# LDR_circuit.net
KiCad netlist of a schematic drawn in EAGLE
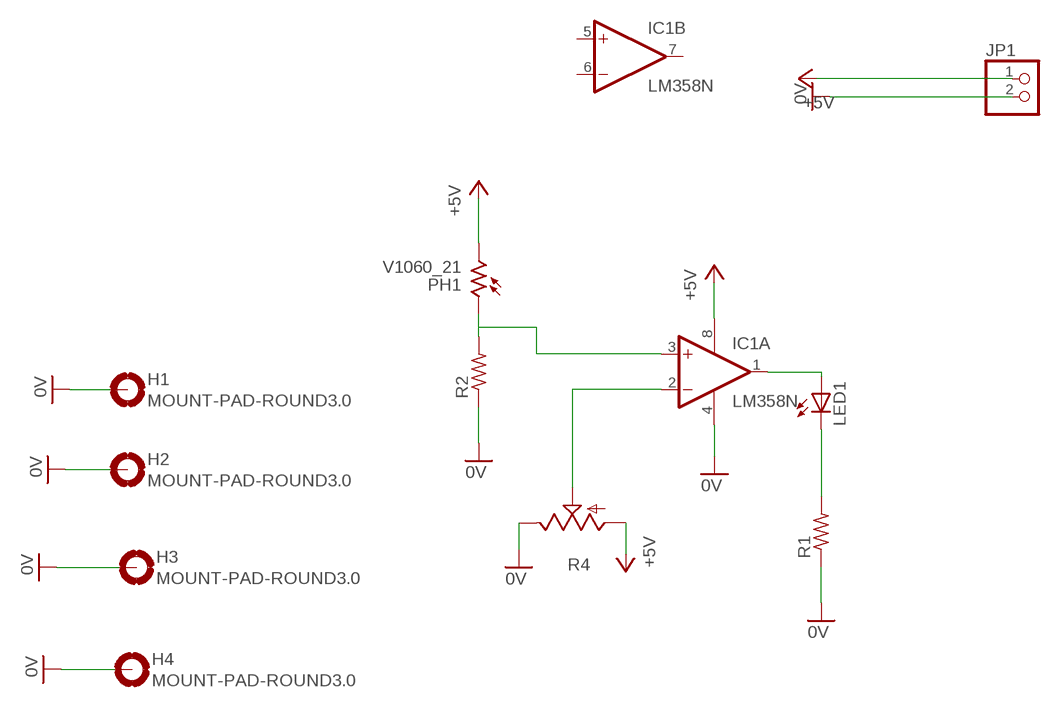
[diagram p0: schematic, sheet 1]

(export (version "E")
  (design (tool "Eeschema 10.0.6"))
  (components
    (comp (ref "H1")
      (value "MOUNT-PAD-ROUND3.0")
      (footprint "eagle-import:3,0-PAD")
      (libsource (lib "eagle-import") (part "MOUNT-PAD-ROUND3.0"))
    )
    (comp (ref "H2")
      (value "MOUNT-PAD-ROUND3.0")
      (footprint "eagle-import:3,0-PAD")
      (libsource (lib "eagle-import") (part "MOUNT-PAD-ROUND3.0"))
    )
    (comp (ref "H3")
      (value "MOUNT-PAD-ROUND3.0")
      (footprint "eagle-import:3,0-PAD")
      (libsource (lib "eagle-import") (part "MOUNT-PAD-ROUND3.0"))
    )
    (comp (ref "H4")
      (value "MOUNT-PAD-ROUND3.0")
      (footprint "eagle-import:3,0-PAD")
      (libsource (lib "eagle-import") (part "MOUNT-PAD-ROUND3.0"))
    )
    (comp (ref "IC1")
      (value "LM358N")
      (footprint "eagle-import:DIL08")
      (libsource (lib "eagle-import") (part "LM358N"))
    )
    (comp (ref "JP1")
      (value "PINHD-1X2")
      (footprint "eagle-import:1X02")
      (libsource (lib "eagle-import") (part "PINHD-1X2"))
    )
    (comp (ref "LED1")
      (value "LED5MM")
      (footprint "eagle-import:LED5MM")
      (libsource (lib "eagle-import") (part "LED5MM"))
    )
    (comp (ref "PH1")
      (value "V1060_21")
      (footprint "eagle-import:TO-5_V10")
      (libsource (lib "eagle-import") (part "?1060V_21"))
    )
    (comp (ref "R1")
      (value "R-US_0207/10")
      (footprint "eagle-import:0207_10")
      (libsource (lib "eagle-import") (part "R-US_0207/10"))
    )
    (comp (ref "R2")
      (value "R-US_0207/10")
      (footprint "eagle-import:0207_10")
      (libsource (lib "eagle-import") (part "R-US_0207/10"))
    )
    (comp (ref "R4")
      (value "TRIM_US-CA6V")
      (footprint "eagle-import:CA6V")
      (libsource (lib "eagle-import") (part "TRIM_US-CA6V"))
    )
  )
  (nets
    (net (code "1") (name "+5V") (class "Default")
      (node (ref "IC1") (pin "8") (pinfunction "V+_8") (pintype "power_in"))
      (node (ref "JP1") (pin "1") (pinfunction "1_1") (pintype "passive"))
      (node (ref "PH1") (pin "2") (pinfunction "2_2") (pintype "passive"))
      (node (ref "R4") (pin "A") (pinfunction "A_A") (pintype "passive"))
    )
    (net (code "2") (name "0V") (class "Default")
      (node (ref "H1") (pin "B3,0") (pinfunction "MOUNT_B3,0") (pintype "passive"))
      (node (ref "H2") (pin "B3,0") (pinfunction "MOUNT_B3,0") (pintype "passive"))
      (node (ref "H3") (pin "B3,0") (pinfunction "MOUNT_B3,0") (pintype "passive"))
      (node (ref "H4") (pin "B3,0") (pinfunction "MOUNT_B3,0") (pintype "passive"))
      (node (ref "IC1") (pin "4") (pinfunction "V-_4") (pintype "power_in"))
      (node (ref "JP1") (pin "2") (pinfunction "2_2") (pintype "passive"))
      (node (ref "R1") (pin "1") (pinfunction "1_1") (pintype "passive"))
      (node (ref "R2") (pin "1") (pinfunction "1_1") (pintype "passive"))
      (node (ref "R4") (pin "E") (pinfunction "E_E") (pintype "passive"))
    )
    (net (code "3") (name "Net-(IC1A-+IN)") (class "Default")
      (node (ref "IC1") (pin "3") (pinfunction "+IN_3") (pintype "input"))
      (node (ref "PH1") (pin "1") (pinfunction "1_1") (pintype "passive"))
      (node (ref "R2") (pin "2") (pinfunction "2_2") (pintype "passive"))
    )
    (net (code "4") (name "Net-(IC1A--IN)") (class "Default")
      (node (ref "IC1") (pin "2") (pinfunction "-IN_2") (pintype "input"))
      (node (ref "R4") (pin "S") (pinfunction "S_S") (pintype "passive"))
    )
    (net (code "5") (name "Net-(IC1A-OUT)") (class "Default")
      (node (ref "IC1") (pin "1") (pinfunction "OUT_1") (pintype "output"))
      (node (ref "LED1") (pin "A") (pinfunction "A_A") (pintype "passive"))
    )
    (net (code "6") (name "Net-(LED1-C)") (class "Default")
      (node (ref "LED1") (pin "K") (pinfunction "C_K") (pintype "passive"))
      (node (ref "R1") (pin "2") (pinfunction "2_2") (pintype "passive"))
    )
    (net (code "7") (name "unconnected-(IC1B-+IN-Pad5)") (class "Default")
      (node (ref "IC1") (pin "5") (pinfunction "+IN_5") (pintype "input"))
    )
    (net (code "8") (name "unconnected-(IC1B--IN-Pad6)") (class "Default")
      (node (ref "IC1") (pin "6") (pinfunction "-IN_6") (pintype "input"))
    )
    (net (code "9") (name "unconnected-(IC1B-OUT-Pad7)") (class "Default")
      (node (ref "IC1") (pin "7") (pinfunction "OUT_7") (pintype "output"))
    )
  )
)
